# 003_HW1_Motor_Controller_Schematic.net
KiCad netlist of a schematic drawn in Altium Designer
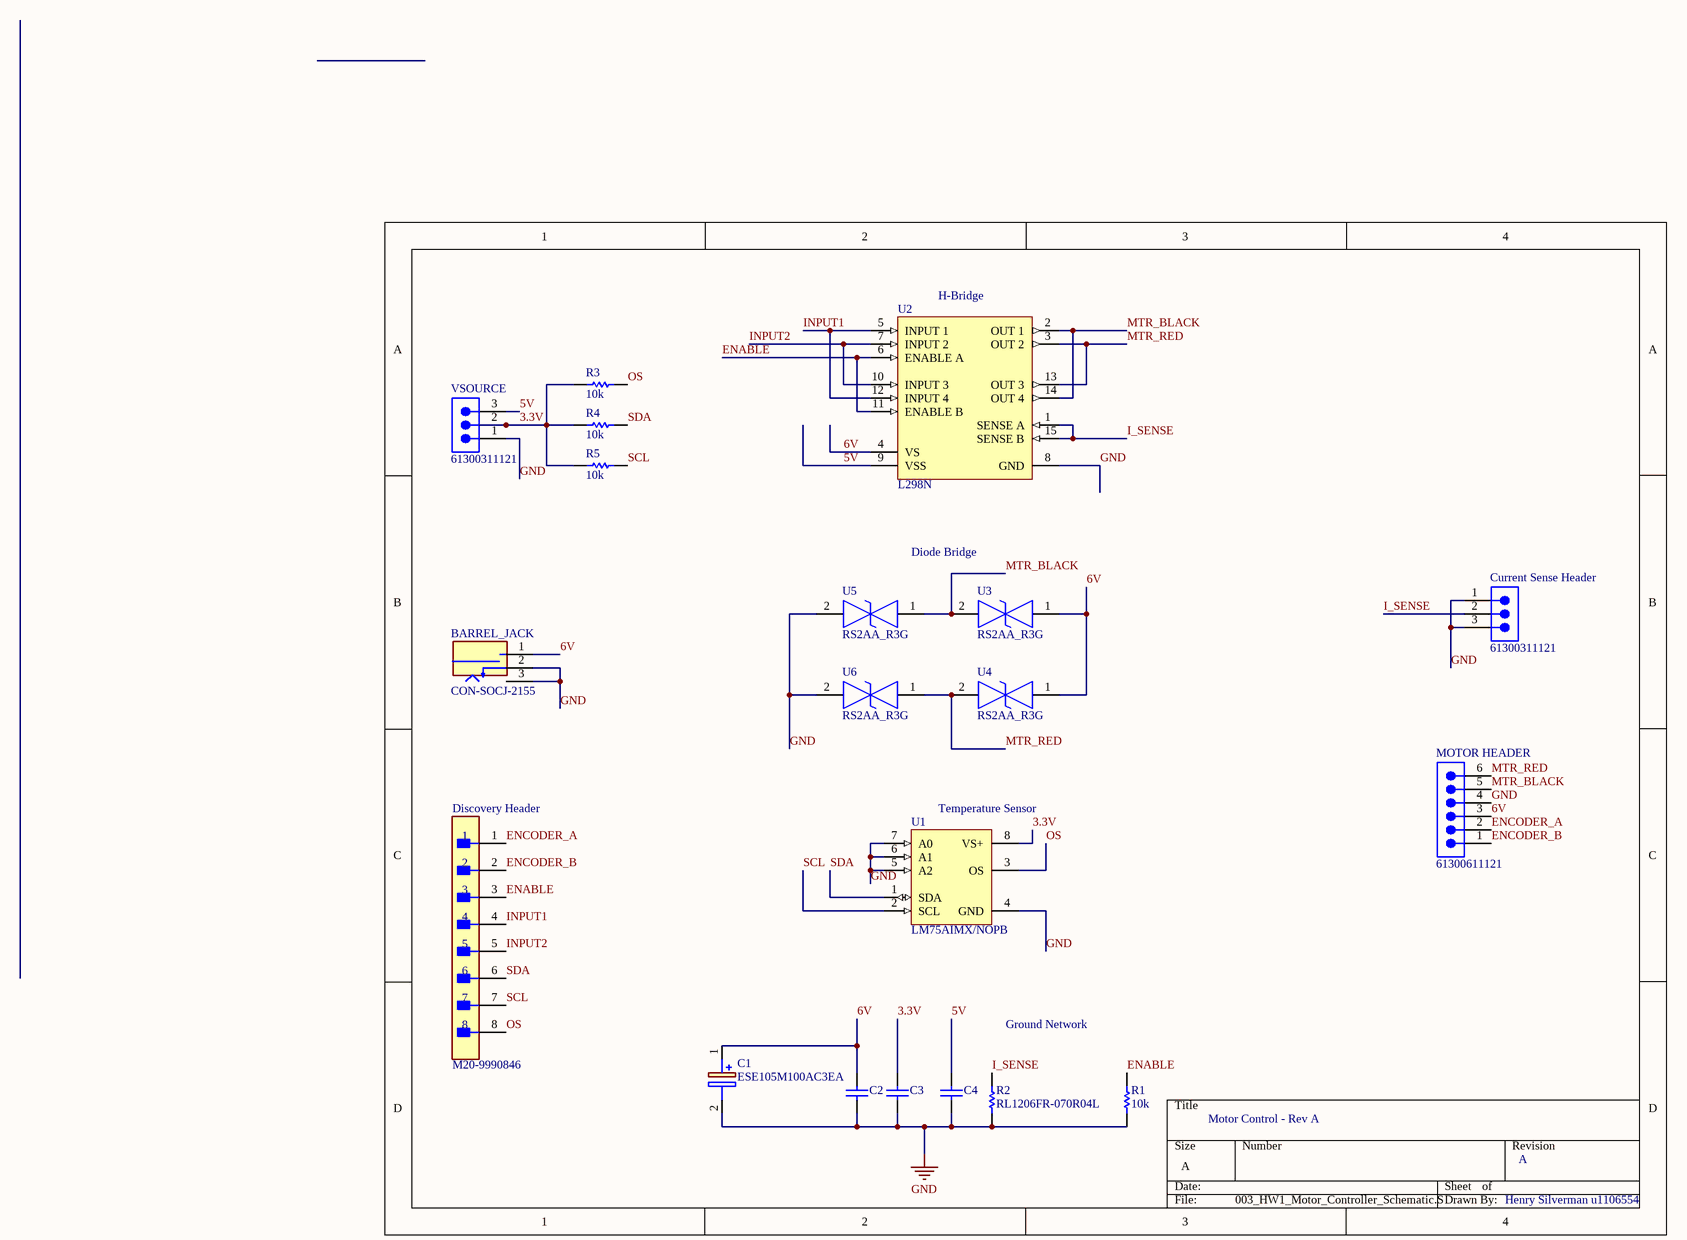
[diagram p0: 003_HW1_Motor_Controller_Schematic.SchDoc]

(export (version "E")
  (design (tool "Eeschema 10.0.6"))
  (components
    (comp (ref "BARREL_JACK")
      (value "CON-SOCJ-2155")
      (footprint "GRAVITECH_CON-SOCJ-2155")
      (description "DC Power Connectors Power Jack/Connector 2.1mm x 5.5mm")
      (fields (field (name "MF") "Gravitech"))
      (libsource (lib "University of Utah ECE") (part "CON-SOCJ-2155"))
    )
    (comp (ref "C1")
      (value "ESE105M100AC3EA")
      (footprint "SamacSys:ESE105M100AC3EA")
      (description "Capacitor Polarised")
      (fields (field (name "MOUSER PART NUMBER") "80-ESE105M100AC3EA"))
      (libsource (lib "*") (part "ESE105M100AC3EA"))
    )
    (comp (ref "C2")
      (value "C1206C104K5RACTU")
      (footprint "KEMT-1206-2_M")
      (description "CAP, Ceramic, 0.1 uF, +/- 10%, 50 V, -55 to 125 degC, 1206 (3216 Metric), RoHS, Tape and Reel")
      (fields (field (name "MANUFACTURER") "Kemet"))
      (libsource (lib "Altium Content Vault") (part "CAP-NP-2"))
    )
    (comp (ref "C3")
      (value "C1206C104K5RACTU")
      (footprint "KEMT-1206-2_M")
      (description "CAP, Ceramic, 0.1 uF, +/- 10%, 50 V, -55 to 125 degC, 1206 (3216 Metric), RoHS, Tape and Reel")
      (fields (field (name "MANUFACTURER") "Kemet"))
      (libsource (lib "Altium Content Vault") (part "CAP-NP-2"))
    )
    (comp (ref "C4")
      (value "C1206C104K5RACTU")
      (footprint "KEMT-1206-2_M")
      (description "CAP, Ceramic, 0.1 uF, +/- 10%, 50 V, -55 to 125 degC, 1206 (3216 Metric), RoHS, Tape and Reel")
      (fields (field (name "MANUFACTURER") "Kemet"))
      (libsource (lib "Altium Content Vault") (part "CAP-NP-2"))
    )
    (comp (ref "Current Sense Header")
      (value "61300311121")
      (footprint "61300311121")
      (libsource (lib "Altium Content Vault") (part "Header_Male_1R_03P"))
    )
    (comp (ref "Discovery Header")
      (value "M20-9990846")
      (footprint "FP-M20-9990846-MFG")
      (description "CONN HEADER VERT 8POS 2.54MM")
      (libsource (lib "Altium Content Vault") (part "99ec2b232beb5d2356d4d77f6a047f0"))
    )
    (comp (ref "MOTOR HEADER")
      (value "61300611121")
      (footprint "61300611121")
      (libsource (lib "Altium Content Vault") (part "Header_Male_1R_06P"))
    )
    (comp (ref "R1")
      (value "10k")
      (footprint "RESC3216X60X45ML15T20")
      (description "Chip Resistor, 0 Ohm, +/- 5%, 0.25 W, -55 to 155 degC, 1206 (3216 Metric)")
      (fields (field (name "TOLERANCE") "5%") (field (name "POWER") "250mW"))
      (libsource (lib "University of Utah ECE") (part "RES-2"))
    )
    (comp (ref "R2")
      (value "RL1206FR-070R04L")
      (footprint "RESC3116X65X40ML10T20")
      (fields (field (name "MANUFACTURER") "Yageo"))
      (libsource (lib "Altium Content Vault") (part "RES"))
    )
    (comp (ref "R3")
      (value "10k")
      (footprint "RESC3216X60X45ML15T20")
      (description "Chip Resistor, 0 Ohm, +/- 5%, 0.25 W, -55 to 155 degC, 1206 (3216 Metric)")
      (fields (field (name "TOLERANCE") "5%") (field (name "POWER") "250mW"))
      (libsource (lib "University of Utah ECE") (part "RES-2"))
    )
    (comp (ref "R4")
      (value "10k")
      (footprint "RESC3216X60X45ML15T20")
      (description "Chip Resistor, 0 Ohm, +/- 5%, 0.25 W, -55 to 155 degC, 1206 (3216 Metric)")
      (fields (field (name "TOLERANCE") "5%") (field (name "POWER") "250mW"))
      (libsource (lib "University of Utah ECE") (part "RES-2"))
    )
    (comp (ref "R5")
      (value "10k")
      (footprint "RESC3216X60X45ML15T20")
      (description "Chip Resistor, 0 Ohm, +/- 5%, 0.25 W, -55 to 155 degC, 1206 (3216 Metric)")
      (fields (field (name "TOLERANCE") "5%") (field (name "POWER") "250mW"))
      (libsource (lib "University of Utah ECE") (part "RES-2"))
    )
    (comp (ref "U1")
      (value "LM75AIMX/NOPB")
      (footprint "D0008A_M")
      (fields (field (name "MANUFACTURER") "Texas Instruments"))
      (libsource (lib "Altium Content Vault") (part "SEN-TEMP-LM75-8"))
    )
    (comp (ref "U2")
      (value "L298N")
      (footprint "STM-FM-15")
      (description "Dual Full-Bridge Driver, 4.8 to 46 V, -40 to 150 degC, 15-Pin FM (MW 15L), RoHS, Tube")
      (fields (field (name "MANUFACTURER") "STMicroelectronics") (field (name "PARTNUMBER") "L298"))
      (libsource (lib "Altium Content Vault") (part "STM-L298-15"))
    )
    (comp (ref "U3")
      (value "RS2AA_R3G")
      (footprint "SamacSys:DIONM5126X250N")
      (description "TVS Diode (Bi-directional)")
      (fields
        (field (name "MANUFACTURER_PART_NUMBER") "RS2AA R3G")
        (field (name "MOUSER PART NUMBER") "821-RS2AAR3G")
      )
      (libsource (lib "*") (part "RS2AA_R3G"))
    )
    (comp (ref "U4")
      (value "RS2AA_R3G")
      (footprint "SamacSys:DIONM5126X250N")
      (description "TVS Diode (Bi-directional)")
      (fields
        (field (name "MANUFACTURER_PART_NUMBER") "RS2AA R3G")
        (field (name "MOUSER PART NUMBER") "821-RS2AAR3G")
      )
      (libsource (lib "*") (part "RS2AA_R3G"))
    )
    (comp (ref "U5")
      (value "RS2AA_R3G")
      (footprint "SamacSys:DIONM5126X250N")
      (description "TVS Diode (Bi-directional)")
      (fields
        (field (name "MANUFACTURER_PART_NUMBER") "RS2AA R3G")
        (field (name "MOUSER PART NUMBER") "821-RS2AAR3G")
      )
      (libsource (lib "*") (part "RS2AA_R3G"))
    )
    (comp (ref "U6")
      (value "RS2AA_R3G")
      (footprint "SamacSys:DIONM5126X250N")
      (description "TVS Diode (Bi-directional)")
      (fields
        (field (name "MANUFACTURER_PART_NUMBER") "RS2AA R3G")
        (field (name "MOUSER PART NUMBER") "821-RS2AAR3G")
      )
      (libsource (lib "*") (part "RS2AA_R3G"))
    )
    (comp (ref "VSOURCE")
      (value "61300311121")
      (footprint "61300311121")
      (libsource (lib "Altium Content Vault") (part "Header_Male_1R_03P"))
    )
  )
  (nets
    (net (code "1") (name "/3.3V") (class "Default")
      (node (ref "C3") (pin "2") (pinfunction "2_2") (pintype "passive"))
      (node (ref "R3") (pin "1") (pinfunction "1_1") (pintype "passive"))
      (node (ref "R4") (pin "1") (pinfunction "1_1") (pintype "passive"))
      (node (ref "R5") (pin "1") (pinfunction "1_1") (pintype "passive"))
      (node (ref "U1") (pin "8") (pinfunction "VS+_8") (pintype "power_in"))
      (node (ref "VSOURCE") (pin "2") (pinfunction "2_2") (pintype "passive"))
    )
    (net (code "2") (name "/5V") (class "Default")
      (node (ref "C4") (pin "2") (pinfunction "2_2") (pintype "passive"))
      (node (ref "U2") (pin "9") (pinfunction "VSS_9") (pintype "power_in"))
      (node (ref "VSOURCE") (pin "3") (pinfunction "3_3") (pintype "passive"))
    )
    (net (code "3") (name "/6V") (class "Default")
      (node (ref "BARREL_JACK") (pin "1") (pinfunction "1_1") (pintype "passive"))
      (node (ref "C1") (pin "1") (pinfunction "+_1") (pintype "passive"))
      (node (ref "C2") (pin "2") (pinfunction "2_2") (pintype "passive"))
      (node (ref "MOTOR HEADER") (pin "3") (pinfunction "3_3") (pintype "passive"))
      (node (ref "U2") (pin "4") (pinfunction "VS_4") (pintype "power_in"))
      (node (ref "U3") (pin "1") (pinfunction "1_1") (pintype "passive"))
      (node (ref "U4") (pin "1") (pinfunction "1_1") (pintype "passive"))
    )
    (net (code "4") (name "/ENABLE") (class "Default")
      (node (ref "Discovery Header") (pin "3") (pinfunction "3_3") (pintype "passive"))
      (node (ref "R1") (pin "1") (pinfunction "1_1") (pintype "passive"))
      (node (ref "U2") (pin "11") (pinfunction "ENABLE_B_11") (pintype "input"))
      (node (ref "U2") (pin "6") (pinfunction "ENABLE_A_6") (pintype "input"))
    )
    (net (code "5") (name "/ENCODER_A") (class "Default")
      (node (ref "Discovery Header") (pin "1") (pinfunction "1_1") (pintype "passive"))
      (node (ref "MOTOR HEADER") (pin "2") (pinfunction "2_2") (pintype "passive"))
    )
    (net (code "6") (name "/ENCODER_B") (class "Default")
      (node (ref "Discovery Header") (pin "2") (pinfunction "2_2") (pintype "passive"))
      (node (ref "MOTOR HEADER") (pin "1") (pinfunction "1_1") (pintype "passive"))
    )
    (net (code "7") (name "/INPUT1") (class "Default")
      (node (ref "Discovery Header") (pin "4") (pinfunction "4_4") (pintype "passive"))
      (node (ref "U2") (pin "12") (pinfunction "INPUT_4_12") (pintype "input"))
      (node (ref "U2") (pin "5") (pinfunction "INPUT_1_5") (pintype "input"))
    )
    (net (code "8") (name "/INPUT2") (class "Default")
      (node (ref "Discovery Header") (pin "5") (pinfunction "5_5") (pintype "passive"))
      (node (ref "U2") (pin "10") (pinfunction "INPUT_3_10") (pintype "input"))
      (node (ref "U2") (pin "7") (pinfunction "INPUT_2_7") (pintype "input"))
    )
    (net (code "9") (name "/I_SENSE") (class "Default")
      (node (ref "Current Sense Header") (pin "2") (pinfunction "2_2") (pintype "passive"))
      (node (ref "R2") (pin "2") (pinfunction "2_2") (pintype "passive"))
      (node (ref "U2") (pin "1") (pinfunction "SENSE_A_1") (pintype "input"))
      (node (ref "U2") (pin "15") (pinfunction "SENSE_B_15") (pintype "input"))
    )
    (net (code "10") (name "/MTR_BLACK") (class "Default")
      (node (ref "MOTOR HEADER") (pin "5") (pinfunction "5_5") (pintype "passive"))
      (node (ref "U2") (pin "14") (pinfunction "OUT_4_14") (pintype "output"))
      (node (ref "U2") (pin "2") (pinfunction "OUT_1_2") (pintype "output"))
      (node (ref "U3") (pin "2") (pinfunction "2_2") (pintype "passive"))
      (node (ref "U5") (pin "1") (pinfunction "1_1") (pintype "passive"))
    )
    (net (code "11") (name "/MTR_RED") (class "Default")
      (node (ref "MOTOR HEADER") (pin "6") (pinfunction "6_6") (pintype "passive"))
      (node (ref "U2") (pin "13") (pinfunction "OUT_3_13") (pintype "output"))
      (node (ref "U2") (pin "3") (pinfunction "OUT_2_3") (pintype "output"))
      (node (ref "U4") (pin "2") (pinfunction "2_2") (pintype "passive"))
      (node (ref "U6") (pin "1") (pinfunction "1_1") (pintype "passive"))
    )
    (net (code "12") (name "/OS") (class "Default")
      (node (ref "Discovery Header") (pin "8") (pinfunction "8_8") (pintype "passive"))
      (node (ref "R3") (pin "2") (pinfunction "2_2") (pintype "passive"))
      (node (ref "U1") (pin "3") (pinfunction "OS_3") (pintype "open_collector"))
    )
    (net (code "13") (name "/SCL") (class "Default")
      (node (ref "Discovery Header") (pin "7") (pinfunction "7_7") (pintype "passive"))
      (node (ref "R5") (pin "2") (pinfunction "2_2") (pintype "passive"))
      (node (ref "U1") (pin "2") (pinfunction "SCL_2") (pintype "input"))
    )
    (net (code "14") (name "/SDA") (class "Default")
      (node (ref "Discovery Header") (pin "6") (pinfunction "6_6") (pintype "passive"))
      (node (ref "R4") (pin "2") (pinfunction "2_2") (pintype "passive"))
      (node (ref "U1") (pin "1") (pinfunction "SDA_1") (pintype "bidirectional"))
    )
    (net (code "15") (name "GND") (class "Default")
      (node (ref "BARREL_JACK") (pin "2") (pinfunction "2_2") (pintype "passive"))
      (node (ref "BARREL_JACK") (pin "3") (pinfunction "3_3") (pintype "passive"))
      (node (ref "C1") (pin "2") (pinfunction "-_2") (pintype "passive"))
      (node (ref "C2") (pin "1") (pinfunction "1_1") (pintype "passive"))
      (node (ref "C3") (pin "1") (pinfunction "1_1") (pintype "passive"))
      (node (ref "C4") (pin "1") (pinfunction "1_1") (pintype "passive"))
      (node (ref "Current Sense Header") (pin "1") (pinfunction "1_1") (pintype "passive"))
      (node (ref "Current Sense Header") (pin "3") (pinfunction "3_3") (pintype "passive"))
      (node (ref "MOTOR HEADER") (pin "4") (pinfunction "4_4") (pintype "passive"))
      (node (ref "R1") (pin "2") (pinfunction "2_2") (pintype "passive"))
      (node (ref "R2") (pin "1") (pinfunction "1_1") (pintype "passive"))
      (node (ref "U1") (pin "4") (pinfunction "GND_4") (pintype "power_in"))
      (node (ref "U1") (pin "5") (pinfunction "A2_5") (pintype "input"))
      (node (ref "U1") (pin "6") (pinfunction "A1_6") (pintype "input"))
      (node (ref "U1") (pin "7") (pinfunction "A0_7") (pintype "input"))
      (node (ref "U2") (pin "8") (pinfunction "GND_8") (pintype "power_in"))
      (node (ref "U5") (pin "2") (pinfunction "2_2") (pintype "passive"))
      (node (ref "U6") (pin "2") (pinfunction "2_2") (pintype "passive"))
      (node (ref "VSOURCE") (pin "1") (pinfunction "1_1") (pintype "passive"))
    )
  )
)
